# PowerDelivery.net
KiCad netlist of a schematic drawn in Altium Designer
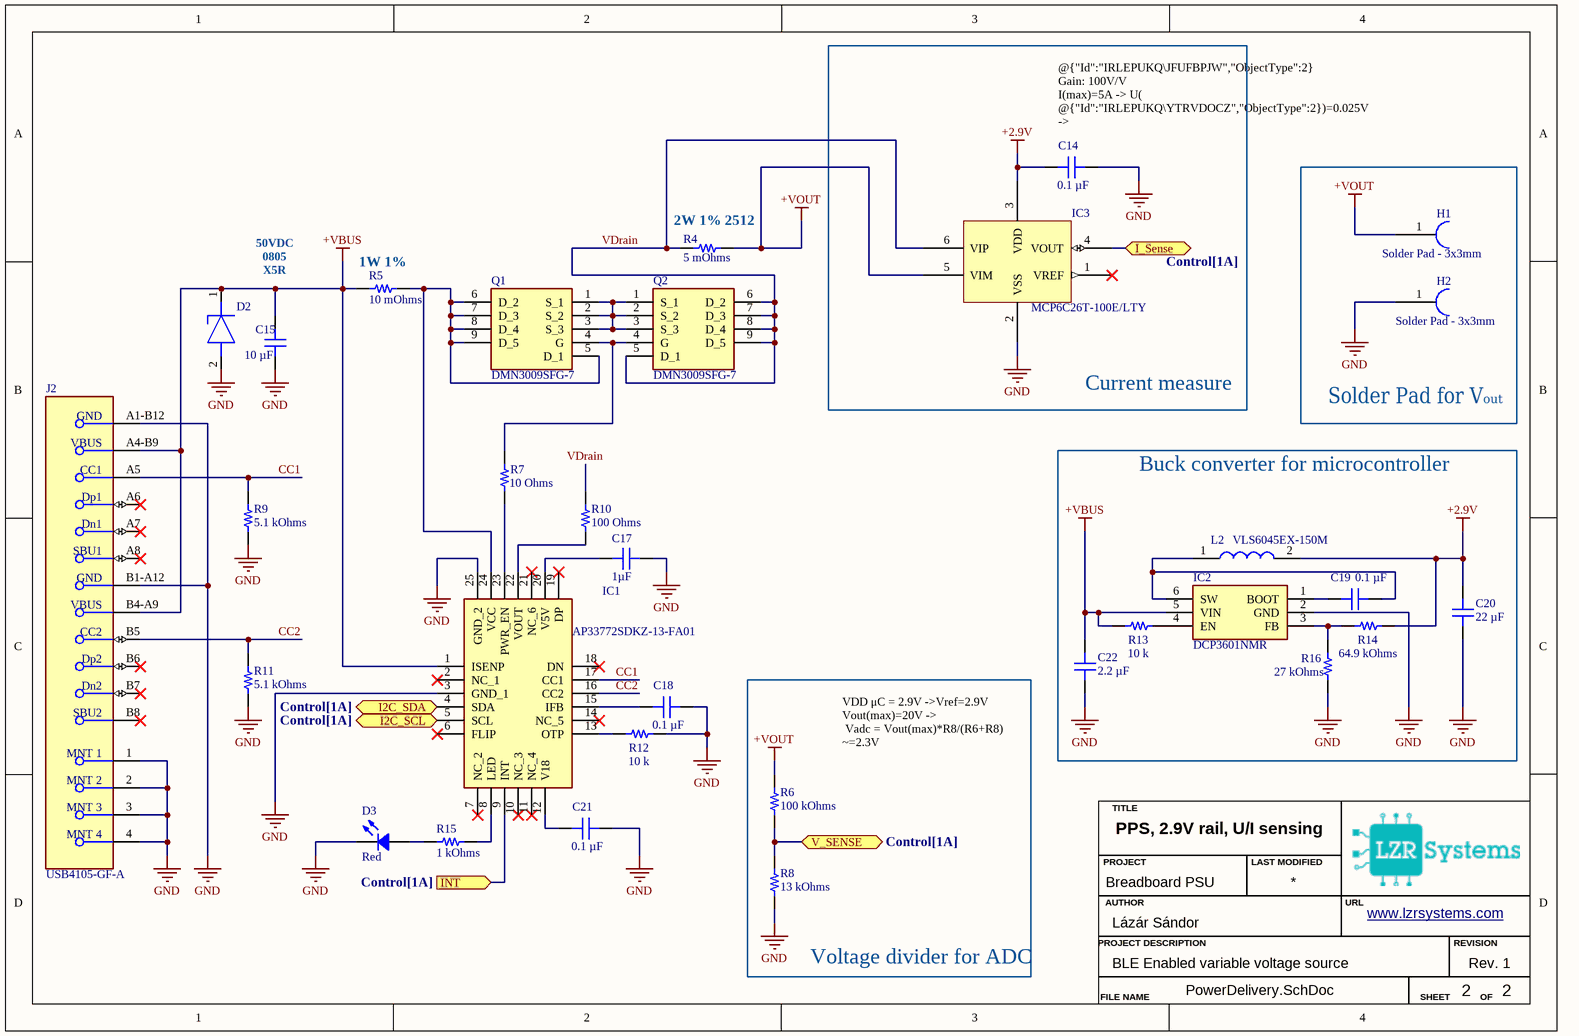
[diagram p0: PowerDelivery.SchDoc]

(export (version "E")
  (design (tool "Eeschema 10.0.6"))
  (components
    (comp (ref "C14")
      (value "0.1 µF")
      (footprint "CAP 0805_2012")
      (description "CAP CER 0.1UF 50V X7R 0805")
      (fields
        (field (name "PART NUMBER") "CC0805MRX7R9BB104")
        (field (name "CAPACITANCE") "0.1 µF")
        (field (name "MANUFACTURER") "Yageo")
      )
      (libsource (lib "Celestial Altium Library - altium_library") (part "Capacitor"))
    )
    (comp (ref "C15")
      (value "10 µF")
      (footprint "MURATA GRM21B 0805_2012")
      (description "CAP CER 10UF 50V X5R 0805")
      (fields
        (field (name "PART NUMBER") "GRM21BR61H106KE43L")
        (field (name "CAPACITANCE") "10 µF")
        (field (name "MANUFACTURER") "Murata Electronics")
      )
      (libsource (lib "Celestial Altium Library - altium_library") (part "Capacitor"))
    )
    (comp (ref "C17")
      (value "1µF")
      (footprint "CAP 0805_2012")
      (description "CAP CER 1UF 25V X7R 0805")
      (fields
        (field (name "PART NUMBER") "08053C105KAT2A")
        (field (name "CAPACITANCE") "1µF")
        (field (name "MANUFACTURER") "AVX Corporation")
      )
      (libsource (lib "Celestial Altium Library - altium_library") (part "Capacitor"))
    )
    (comp (ref "C18")
      (value "0.1 µF")
      (footprint "CAP 0805_2012")
      (description "CAP CER 0.1UF 50V X7R 0805")
      (fields
        (field (name "PART NUMBER") "CC0805MRX7R9BB104")
        (field (name "CAPACITANCE") "0.1 µF")
        (field (name "MANUFACTURER") "Yageo")
      )
      (libsource (lib "Celestial Altium Library - altium_library") (part "Capacitor"))
    )
    (comp (ref "C19")
      (value "0.1 µF")
      (footprint "CAP 0805_2012")
      (description "CAP CER 0.1UF 50V X7R 0805")
      (fields
        (field (name "PART NUMBER") "CC0805MRX7R9BB104")
        (field (name "CAPACITANCE") "0.1 µF")
        (field (name "MANUFACTURER") "Yageo")
      )
      (libsource (lib "Celestial Altium Library - altium_library") (part "Capacitor"))
    )
    (comp (ref "C20")
      (value "22 µF")
      (footprint "CAP 1206_3216 - 0.8MM")
      (description "CAP CER 22UF 16V X5R 1206")
      (fields
        (field (name "PART NUMBER") "CL31A226MOCLNNC")
        (field (name "CAPACITANCE") "22 µF")
        (field (name "MANUFACTURER") "Samsung Electro-Mechanics")
      )
      (libsource (lib "Celestial Altium Library - altium_library") (part "Capacitor"))
    )
    (comp (ref "C21")
      (value "0.1 µF")
      (footprint "CAP 0805_2012")
      (description "CAP CER 0.1UF 50V X7R 0805")
      (fields
        (field (name "PART NUMBER") "CC0805MRX7R9BB104")
        (field (name "CAPACITANCE") "0.1 µF")
        (field (name "MANUFACTURER") "Yageo")
      )
      (libsource (lib "Celestial Altium Library - altium_library") (part "Capacitor"))
    )
    (comp (ref "C22")
      (value "2.2 µF")
      (footprint "CAP 1206_3216 - 0.8MM")
      (description "CAP CER 2.2UF 50V X7R 1206")
      (fields
        (field (name "PART NUMBER") "GCJ31CR71H225KA12K")
        (field (name "CAPACITANCE") "2.2 µF")
        (field (name "MANUFACTURER") "Murata Electronics")
      )
      (libsource (lib "Celestial Altium Library - altium_library") (part "Capacitor"))
    )
    (comp (ref "D2")
      (value "PESD24VS1UA,115")
      (footprint "SamacSys:SOD2512X110N")
      (description "Diode ESD (Uni-directional)")
      (fields (field (name "MOUSER PART NUMBER") "771-PESD24VS1UA115"))
      (libsource (lib "*") (part "PESD24VS1UA,115"))
    )
    (comp (ref "D3")
      (value "Red")
      (footprint "LED 1206_3216 RED")
      (description "LED RED 1206 SMD")
      (fields (field (name "PART NUMBER") "5990210007F") (field (name "MANUFACTURER") "Dialight"))
      (libsource (lib "Celestial Altium Library - altium_library") (part "LED"))
    )
    (comp (ref "H1")
      (value "Solder Pad - 3x3mm")
      (footprint "Solder Pad - 3x3mm-Footprint-1")
      (description "Wire to board solder pad rectangular 3x3mm")
      (libsource (lib "Sandor Lazar") (part "Solder Pad - 3x3mm"))
    )
    (comp (ref "H2")
      (value "Solder Pad - 3x3mm")
      (footprint "Solder Pad - 3x3mm-Footprint-1")
      (description "Wire to board solder pad rectangular 3x3mm")
      (libsource (lib "Sandor Lazar") (part "Solder Pad - 3x3mm"))
    )
    (comp (ref "IC1")
      (value "AP33772SDKZ-13-FA01")
      (footprint "SamacSys:AP33772SDKZ13FA01")
      (description "Integrated Circuit")
      (fields (field (name "MOUSER PART NUMBER") "621-P33772SDKZ13FA01"))
      (libsource (lib "*") (part "AP33772SDKZ-13-FA01"))
    )
    (comp (ref "IC2")
      (value "DCP3601NMR")
      (footprint "SamacSys:SOT95P280X125-6N")
      (description "Integrated Circuit")
      (fields (field (name "MOUSER PART NUMBER") "511-DCP3601NMR"))
      (libsource (lib "SamacSys") (part "DCP3601NMR"))
    )
    (comp (ref "IC3")
      (value "MCP6C26T-100E/LTY")
      (footprint "SOT65P210X80-6N")
      (description "Current Sense Amplifiers Zero-Drift, Current Sense Amplifier, Gain = 100V/V, REEL")
      (libsource (lib "Sandor Lazar") (part "MCP6C26T-100E_LTY-Symbol-1"))
    )
    (comp (ref "J2")
      (value "USB4105-GF-A")
      (footprint "FP-USB4105-GF-A-MFG")
      (description "Conn USB 2.0 Type C RCP 24 POS 0.3mm/0.5mm Solder RA SMD 24 Terminal 1 Port T/R")
      (libsource (lib "Sandor Lazar") (part "e7c17a616881a82b79941196b4bec10"))
    )
    (comp (ref "L2")
      (value "VLS6045EX-150M")
      (footprint "SamacSys:VLS6045")
      (description "Inductor")
      (fields (field (name "MOUSER PART NUMBER") "810-VLS6045EX-150M"))
      (libsource (lib "SamacSys") (part "VLS6045EX-150M"))
    )
    (comp (ref "Q1")
      (value "DMN3009SFG-7")
      (footprint "SamacSys:DMTH8008LFGQ7")
      (description "MOSFET (N-Channel)")
      (fields (field (name "MOUSER PART NUMBER") "621-DMN3009SFG-7"))
      (libsource (lib "*") (part "DMN3009SFG-7"))
    )
    (comp (ref "Q2")
      (value "DMN3009SFG-7")
      (footprint "SamacSys:DMTH8008LFGQ7")
      (description "MOSFET (N-Channel)")
      (fields (field (name "MOUSER PART NUMBER") "621-DMN3009SFG-7"))
      (libsource (lib "") (part "DMN3009SFG-7_1"))
    )
    (comp (ref "R4")
      (value "5 mOhms")
      (footprint "STACKPOLE CSM2512")
      (description "RES 0.04 OHM 1% 3W 2512")
      (fields
        (field (name "PART NUMBER") "CSM2512FT40L0")
        (field (name "MANUFACTURER") "Stackpole Electronics Inc")
      )
      (libsource (lib "Celestial Altium Library - altium_library") (part "Resistor"))
    )
    (comp (ref "R5")
      (value "10 mOhms")
      (footprint "RES 1206_3216")
      (description "RES 0.01 OHM 1% 1W 1206")
      (fields
        (field (name "PART NUMBER") "TLRP2B10WR010FTD")
        (field (name "MANUFACTURER") "TE Connectivity Passive Product")
      )
      (libsource (lib "Celestial Altium Library - altium_library") (part "Resistor"))
    )
    (comp (ref "R6")
      (value "100 kOhms")
      (footprint "RES 0805_2012")
      (description "RES SMD 100K OHM 1% 1/8W 0805")
      (fields (field (name "PART NUMBER") "CRCW0805100KFKEA") (field (name "MANUFACTURER") "Vishay Dale"))
      (libsource (lib "Celestial Altium Library - altium_library") (part "Resistor"))
    )
    (comp (ref "R7")
      (value "10 Ohms")
      (footprint "RES 0805_2012")
      (description "RES 10 OHM 1% 1/8W 0805")
      (fields (field (name "PART NUMBER") "CRCW080510R0FKEAC") (field (name "MANUFACTURER") "Vishay Dale"))
      (libsource (lib "Celestial Altium Library - altium_library") (part "Resistor"))
    )
    (comp (ref "R8")
      (value "13 kOhms")
      (footprint "RES 0805_2012")
      (description "RES SMD 11K OHM 1% 1/2W 0805")
      (fields (field (name "PART NUMBER") "CRCW080511K0FKEAHP") (field (name "MANUFACTURER") "Vishay Dale"))
      (libsource (lib "Celestial Altium Library - altium_library") (part "Resistor"))
    )
    (comp (ref "R9")
      (value "5.1 kOhms")
      (footprint "YAGEO RES 0805_2012")
      (description "RES SMD 5.1K OHM 0.1% 1/8W 0805")
      (fields (field (name "PART NUMBER") "RT0805BRD075K1L") (field (name "MANUFACTURER") "Yageo"))
      (libsource (lib "Celestial Altium Library - altium_library") (part "Resistor"))
    )
    (comp (ref "R10")
      (value "100 Ohms")
      (footprint "RES 0805_2012")
      (description "RES 100 OHM 1% 1/8W 0805")
      (fields (field (name "PART NUMBER") "CRCW0805100RFKEAC") (field (name "MANUFACTURER") "Vishay Dale"))
      (libsource (lib "Celestial Altium Library - altium_library") (part "Resistor"))
    )
    (comp (ref "R11")
      (value "5.1 kOhms")
      (footprint "YAGEO RES 0805_2012")
      (description "RES SMD 5.1K OHM 0.1% 1/8W 0805")
      (fields (field (name "PART NUMBER") "RT0805BRD075K1L") (field (name "MANUFACTURER") "Yageo"))
      (libsource (lib "Celestial Altium Library - altium_library") (part "Resistor"))
    )
    (comp (ref "R12")
      (value "10 k")
      (footprint "RES 0805_2012")
      (description "RES 10K OHM 0.1% 1/10W 0805")
      (fields
        (field (name "PART NUMBER") "RNCS0805BKE10K0")
        (field (name "MANUFACTURER") "Stackpole Electronics Inc")
      )
      (libsource (lib "Celestial Altium Library - altium_library") (part "Resistor"))
    )
    (comp (ref "R13")
      (value "10 k")
      (footprint "RES 0805_2012")
      (description "RES 10K OHM 0.1% 1/10W 0805")
      (fields
        (field (name "PART NUMBER") "RNCS0805BKE10K0")
        (field (name "MANUFACTURER") "Stackpole Electronics Inc")
      )
      (libsource (lib "Celestial Altium Library - altium_library") (part "Resistor"))
    )
    (comp (ref "R14")
      (value "64.9 kOhms")
      (footprint "RES 0805_2012")
      (description "RES 64.9K OHM 1% 1/8W 0805")
      (fields
        (field (name "PART NUMBER") "RMCF0805FT64K9")
        (field (name "MANUFACTURER") "Stackpole Electronics Inc")
      )
      (libsource (lib "Celestial Altium Library - altium_library") (part "Resistor"))
    )
    (comp (ref "R15")
      (value "1 kOhms")
      (footprint "RES 0805_2012")
      (description "RES SMD 1K OHM 0.01% 1/5W 0805")
      (fields
        (field (name "PART NUMBER") "Y40221K00000T0R")
        (field (name "MANUFACTURER") "Vishay Foil Resistors (Division of Vishay Precision Group)")
      )
      (libsource (lib "Celestial Altium Library - altium_library") (part "Resistor"))
    )
    (comp (ref "R16")
      (value "27 kOhms")
      (footprint "YAGEO RES 0805_2012")
      (description "RES SMD 27K OHM 5% 1/8W 0805")
      (fields (field (name "PART NUMBER") "AC0805JR-0727KL") (field (name "MANUFACTURER") "Yageo"))
      (libsource (lib "Celestial Altium Library - altium_library") (part "Resistor"))
    )
  )
  (nets
    (net (code "1") (name "+2.9V") (class "Default")
      (node (ref "C14") (pin "2") (pinfunction "2_2") (pintype "passive"))
      (node (ref "C20") (pin "2") (pinfunction "2_2") (pintype "passive"))
      (node (ref "IC3") (pin "3") (pinfunction "VDD_3") (pintype "power_in"))
      (node (ref "L2") (pin "2") (pinfunction "2_2") (pintype "passive"))
      (node (ref "R14") (pin "2") (pinfunction "2_2") (pintype "passive"))
    )
    (net (code "2") (name "+VBUS") (class "Default")
      (node (ref "C15") (pin "2") (pinfunction "2_2") (pintype "passive"))
      (node (ref "C22") (pin "2") (pinfunction "2_2") (pintype "passive"))
      (node (ref "D2") (pin "1") (pinfunction "K_1") (pintype "passive"))
      (node (ref "IC1") (pin "1") (pinfunction "ISENP_1") (pintype "passive"))
      (node (ref "IC2") (pin "5") (pinfunction "VIN_5") (pintype "passive"))
      (node (ref "J2") (pin "A4-B9") (pinfunction "VBUS_A4-B9") (pintype "power_in"))
      (node (ref "J2") (pin "B4-A9") (pinfunction "VBUS_B4-A9") (pintype "power_in"))
      (node (ref "R13") (pin "1") (pinfunction "1_1") (pintype "passive"))
      (node (ref "R5") (pin "1") (pinfunction "1_1") (pintype "passive"))
    )
    (net (code "3") (name "+VOUT") (class "Default")
      (node (ref "H1") (pin "1") (pinfunction "1_1") (pintype "passive"))
      (node (ref "IC3") (pin "5") (pinfunction "VIM_5") (pintype "passive"))
      (node (ref "R4") (pin "2") (pinfunction "2_2") (pintype "passive"))
      (node (ref "R6") (pin "2") (pinfunction "2_2") (pintype "passive"))
    )
    (net (code "4") (name "/CC1") (class "Default")
      (node (ref "IC1") (pin "17") (pinfunction "CC1_17") (pintype "passive"))
      (node (ref "J2") (pin "A5") (pinfunction "CC1_A5") (pintype "power_in"))
      (node (ref "R9") (pin "2") (pinfunction "2_2") (pintype "passive"))
    )
    (net (code "5") (name "/CC2") (class "Default")
      (node (ref "IC1") (pin "16") (pinfunction "CC2_16") (pintype "passive"))
      (node (ref "J2") (pin "B5") (pinfunction "CC2_B5") (pintype "bidirectional"))
      (node (ref "R11") (pin "2") (pinfunction "2_2") (pintype "passive"))
    )
    (net (code "6") (name "/I2C_SCL") (class "Default")
      (node (ref "IC1") (pin "5") (pinfunction "SCL_5") (pintype "passive"))
    )
    (net (code "7") (name "/I2C_SDA") (class "Default")
      (node (ref "IC1") (pin "4") (pinfunction "SDA_4") (pintype "passive"))
    )
    (net (code "8") (name "/INT") (class "Default")
      (node (ref "IC1") (pin "9") (pinfunction "INT_9") (pintype "passive"))
    )
    (net (code "9") (name "/I_Sense") (class "Default")
      (node (ref "IC3") (pin "4") (pinfunction "VOUT_4") (pintype "bidirectional"))
    )
    (net (code "10") (name "/VDrain") (class "Default")
      (node (ref "IC3") (pin "6") (pinfunction "VIP_6") (pintype "passive"))
      (node (ref "Q2") (pin "5") (pinfunction "D_1_5") (pintype "passive"))
      (node (ref "Q2") (pin "6") (pinfunction "D_2_6") (pintype "passive"))
      (node (ref "Q2") (pin "7") (pinfunction "D_3_7") (pintype "passive"))
      (node (ref "Q2") (pin "8") (pinfunction "D_4_8") (pintype "passive"))
      (node (ref "Q2") (pin "9") (pinfunction "D_5_9") (pintype "passive"))
      (node (ref "R10") (pin "2") (pinfunction "2_2") (pintype "passive"))
      (node (ref "R4") (pin "1") (pinfunction "1_1") (pintype "passive"))
    )
    (net (code "11") (name "/V_SENSE") (class "Default")
      (node (ref "R6") (pin "1") (pinfunction "1_1") (pintype "passive"))
      (node (ref "R8") (pin "2") (pinfunction "2_2") (pintype "passive"))
    )
    (net (code "12") (name "GND") (class "Default")
      (node (ref "C14") (pin "1") (pinfunction "1_1") (pintype "passive"))
      (node (ref "C15") (pin "1") (pinfunction "1_1") (pintype "passive"))
      (node (ref "C17") (pin "2") (pinfunction "2_2") (pintype "passive"))
      (node (ref "C18") (pin "1") (pinfunction "1_1") (pintype "passive"))
      (node (ref "C20") (pin "1") (pinfunction "1_1") (pintype "passive"))
      (node (ref "C21") (pin "1") (pinfunction "1_1") (pintype "passive"))
      (node (ref "C22") (pin "1") (pinfunction "1_1") (pintype "passive"))
      (node (ref "D2") (pin "2") (pinfunction "A_2") (pintype "passive"))
      (node (ref "D3") (pin "2") (pinfunction "2_2") (pintype "passive"))
      (node (ref "H2") (pin "1") (pinfunction "1_1") (pintype "passive"))
      (node (ref "IC1") (pin "25") (pinfunction "GND_2_25") (pintype "passive"))
      (node (ref "IC1") (pin "3") (pinfunction "GND_1_3") (pintype "passive"))
      (node (ref "IC2") (pin "2") (pinfunction "GND_2") (pintype "passive"))
      (node (ref "IC3") (pin "2") (pinfunction "VSS_2") (pintype "power_in"))
      (node (ref "J2") (pin "1") (pinfunction "MNT_1_1") (pintype "power_in"))
      (node (ref "J2") (pin "2") (pinfunction "MNT_2_2") (pintype "power_in"))
      (node (ref "J2") (pin "3") (pinfunction "MNT_3_3") (pintype "power_in"))
      (node (ref "J2") (pin "4") (pinfunction "MNT_4_4") (pintype "power_in"))
      (node (ref "J2") (pin "A1-B12") (pinfunction "GND_A1-B12") (pintype "power_in"))
      (node (ref "J2") (pin "B1-A12") (pinfunction "GND_B1-A12") (pintype "power_in"))
      (node (ref "R11") (pin "1") (pinfunction "1_1") (pintype "passive"))
      (node (ref "R12") (pin "2") (pinfunction "2_2") (pintype "passive"))
      (node (ref "R16") (pin "1") (pinfunction "1_1") (pintype "passive"))
      (node (ref "R8") (pin "1") (pinfunction "1_1") (pintype "passive"))
      (node (ref "R9") (pin "1") (pinfunction "1_1") (pintype "passive"))
    )
    (net (code "13") (name "Net-(D3-Pad1)") (class "Default")
      (node (ref "D3") (pin "1") (pinfunction "1_1") (pintype "passive"))
      (node (ref "R15") (pin "1") (pinfunction "1_1") (pintype "passive"))
    )
    (net (code "14") (name "Net-(IC1-IFB)") (class "Default")
      (node (ref "C18") (pin "2") (pinfunction "2_2") (pintype "passive"))
      (node (ref "IC1") (pin "15") (pinfunction "IFB_15") (pintype "passive"))
    )
    (net (code "15") (name "Net-(IC1-LED)") (class "Default")
      (node (ref "IC1") (pin "8") (pinfunction "LED_8") (pintype "passive"))
      (node (ref "R15") (pin "2") (pinfunction "2_2") (pintype "passive"))
    )
    (net (code "16") (name "Net-(IC1-OTP)") (class "Default")
      (node (ref "IC1") (pin "13") (pinfunction "OTP_13") (pintype "passive"))
      (node (ref "R12") (pin "1") (pinfunction "1_1") (pintype "passive"))
    )
    (net (code "17") (name "Net-(IC1-PWR_EN)") (class "Default")
      (node (ref "IC1") (pin "23") (pinfunction "PWR_EN_23") (pintype "passive"))
      (node (ref "R7") (pin "1") (pinfunction "1_1") (pintype "passive"))
    )
    (net (code "18") (name "Net-(IC1-V5V)") (class "Default")
      (node (ref "C17") (pin "1") (pinfunction "1_1") (pintype "passive"))
      (node (ref "IC1") (pin "20") (pinfunction "V5V_20") (pintype "passive"))
    )
    (net (code "19") (name "Net-(IC1-V18)") (class "Default")
      (node (ref "C21") (pin "2") (pinfunction "2_2") (pintype "passive"))
      (node (ref "IC1") (pin "12") (pinfunction "V18_12") (pintype "passive"))
    )
    (net (code "20") (name "Net-(IC1-VCC)") (class "Default")
      (node (ref "IC1") (pin "24") (pinfunction "VCC_24") (pintype "passive"))
      (node (ref "Q1") (pin "5") (pinfunction "D_1_5") (pintype "passive"))
      (node (ref "Q1") (pin "6") (pinfunction "D_2_6") (pintype "passive"))
      (node (ref "Q1") (pin "7") (pinfunction "D_3_7") (pintype "passive"))
      (node (ref "Q1") (pin "8") (pinfunction "D_4_8") (pintype "passive"))
      (node (ref "Q1") (pin "9") (pinfunction "D_5_9") (pintype "passive"))
      (node (ref "R5") (pin "2") (pinfunction "2_2") (pintype "passive"))
    )
    (net (code "21") (name "Net-(IC1-VOUT)") (class "Default")
      (node (ref "IC1") (pin "22") (pinfunction "VOUT_22") (pintype "passive"))
      (node (ref "R10") (pin "1") (pinfunction "1_1") (pintype "passive"))
    )
    (net (code "22") (name "Net-(IC2-BOOT)") (class "Default")
      (node (ref "C19") (pin "1") (pinfunction "1_1") (pintype "passive"))
      (node (ref "IC2") (pin "1") (pinfunction "BOOT_1") (pintype "passive"))
    )
    (net (code "23") (name "Net-(IC2-EN)") (class "Default")
      (node (ref "IC2") (pin "4") (pinfunction "EN_4") (pintype "passive"))
      (node (ref "R13") (pin "2") (pinfunction "2_2") (pintype "passive"))
    )
    (net (code "24") (name "Net-(IC2-FB)") (class "Default")
      (node (ref "IC2") (pin "3") (pinfunction "FB_3") (pintype "passive"))
      (node (ref "R14") (pin "1") (pinfunction "1_1") (pintype "passive"))
      (node (ref "R16") (pin "2") (pinfunction "2_2") (pintype "passive"))
    )
    (net (code "25") (name "Net-(IC2-SW)") (class "Default")
      (node (ref "C19") (pin "2") (pinfunction "2_2") (pintype "passive"))
      (node (ref "IC2") (pin "6") (pinfunction "SW_6") (pintype "passive"))
      (node (ref "L2") (pin "1") (pinfunction "1_1") (pintype "passive"))
    )
    (net (code "26") (name "Net-(Q1-G)") (class "Default")
      (node (ref "Q1") (pin "4") (pinfunction "G_4") (pintype "passive"))
      (node (ref "Q2") (pin "4") (pinfunction "G_4") (pintype "passive"))
      (node (ref "R7") (pin "2") (pinfunction "2_2") (pintype "passive"))
    )
    (net (code "27") (name "Net-(Q1-S_1)") (class "Default")
      (node (ref "Q1") (pin "1") (pinfunction "S_1_1") (pintype "passive"))
      (node (ref "Q1") (pin "2") (pinfunction "S_2_2") (pintype "passive"))
      (node (ref "Q1") (pin "3") (pinfunction "S_3_3") (pintype "passive"))
      (node (ref "Q2") (pin "1") (pinfunction "S_1_1") (pintype "passive"))
      (node (ref "Q2") (pin "2") (pinfunction "S_2_2") (pintype "passive"))
      (node (ref "Q2") (pin "3") (pinfunction "S_3_3") (pintype "passive"))
    )
    (net (code "28") (name "unconnected-(IC1-DN-Pad18)") (class "Default")
      (node (ref "IC1") (pin "18") (pinfunction "DN_18") (pintype "passive+no_connect"))
    )
    (net (code "29") (name "unconnected-(IC1-DP-Pad19)") (class "Default")
      (node (ref "IC1") (pin "19") (pinfunction "DP_19") (pintype "passive+no_connect"))
    )
    (net (code "30") (name "unconnected-(IC1-FLIP-Pad6)") (class "Default")
      (node (ref "IC1") (pin "6") (pinfunction "FLIP_6") (pintype "passive+no_connect"))
    )
    (net (code "31") (name "unconnected-(IC1-NC_1-Pad2)") (class "Default")
      (node (ref "IC1") (pin "2") (pinfunction "NC_1_2") (pintype "passive+no_connect"))
    )
    (net (code "32") (name "unconnected-(IC1-NC_2-Pad7)") (class "Default")
      (node (ref "IC1") (pin "7") (pinfunction "NC_2_7") (pintype "passive+no_connect"))
    )
    (net (code "33") (name "unconnected-(IC1-NC_3-Pad10)") (class "Default")
      (node (ref "IC1") (pin "10") (pinfunction "NC_3_10") (pintype "passive+no_connect"))
    )
    (net (code "34") (name "unconnected-(IC1-NC_4-Pad11)") (class "Default")
      (node (ref "IC1") (pin "11") (pinfunction "NC_4_11") (pintype "passive+no_connect"))
    )
    (net (code "35") (name "unconnected-(IC1-NC_5-Pad14)") (class "Default")
      (node (ref "IC1") (pin "14") (pinfunction "NC_5_14") (pintype "passive+no_connect"))
    )
    (net (code "36") (name "unconnected-(IC1-NC_6-Pad21)") (class "Default")
      (node (ref "IC1") (pin "21") (pinfunction "NC_6_21") (pintype "passive+no_connect"))
    )
    (net (code "37") (name "unconnected-(IC3-VREF-Pad1)") (class "Default")
      (node (ref "IC3") (pin "1") (pinfunction "VREF_1") (pintype "output+no_connect"))
    )
    (net (code "38") (name "unconnected-(J2-Dn1-PadA7)") (class "Default")
      (node (ref "J2") (pin "A7") (pinfunction "Dn1_A7") (pintype "bidirectional+no_connect"))
    )
    (net (code "39") (name "unconnected-(J2-Dn2-PadB7)") (class "Default")
      (node (ref "J2") (pin "B7") (pinfunction "Dn2_B7") (pintype "bidirectional+no_connect"))
    )
    (net (code "40") (name "unconnected-(J2-Dp1-PadA6)") (class "Default")
      (node (ref "J2") (pin "A6") (pinfunction "Dp1_A6") (pintype "bidirectional+no_connect"))
    )
    (net (code "41") (name "unconnected-(J2-Dp2-PadB6)") (class "Default")
      (node (ref "J2") (pin "B6") (pinfunction "Dp2_B6") (pintype "bidirectional+no_connect"))
    )
    (net (code "42") (name "unconnected-(J2-SBU1-PadA8)") (class "Default")
      (node (ref "J2") (pin "A8") (pinfunction "SBU1_A8") (pintype "bidirectional+no_connect"))
    )
    (net (code "43") (name "unconnected-(J2-SBU2-PadB8)") (class "Default")
      (node (ref "J2") (pin "B8") (pinfunction "SBU2_B8") (pintype "power_in+no_connect"))
    )
  )
)
